# afe.net
KiCad netlist of a schematic drawn in Altium Designer
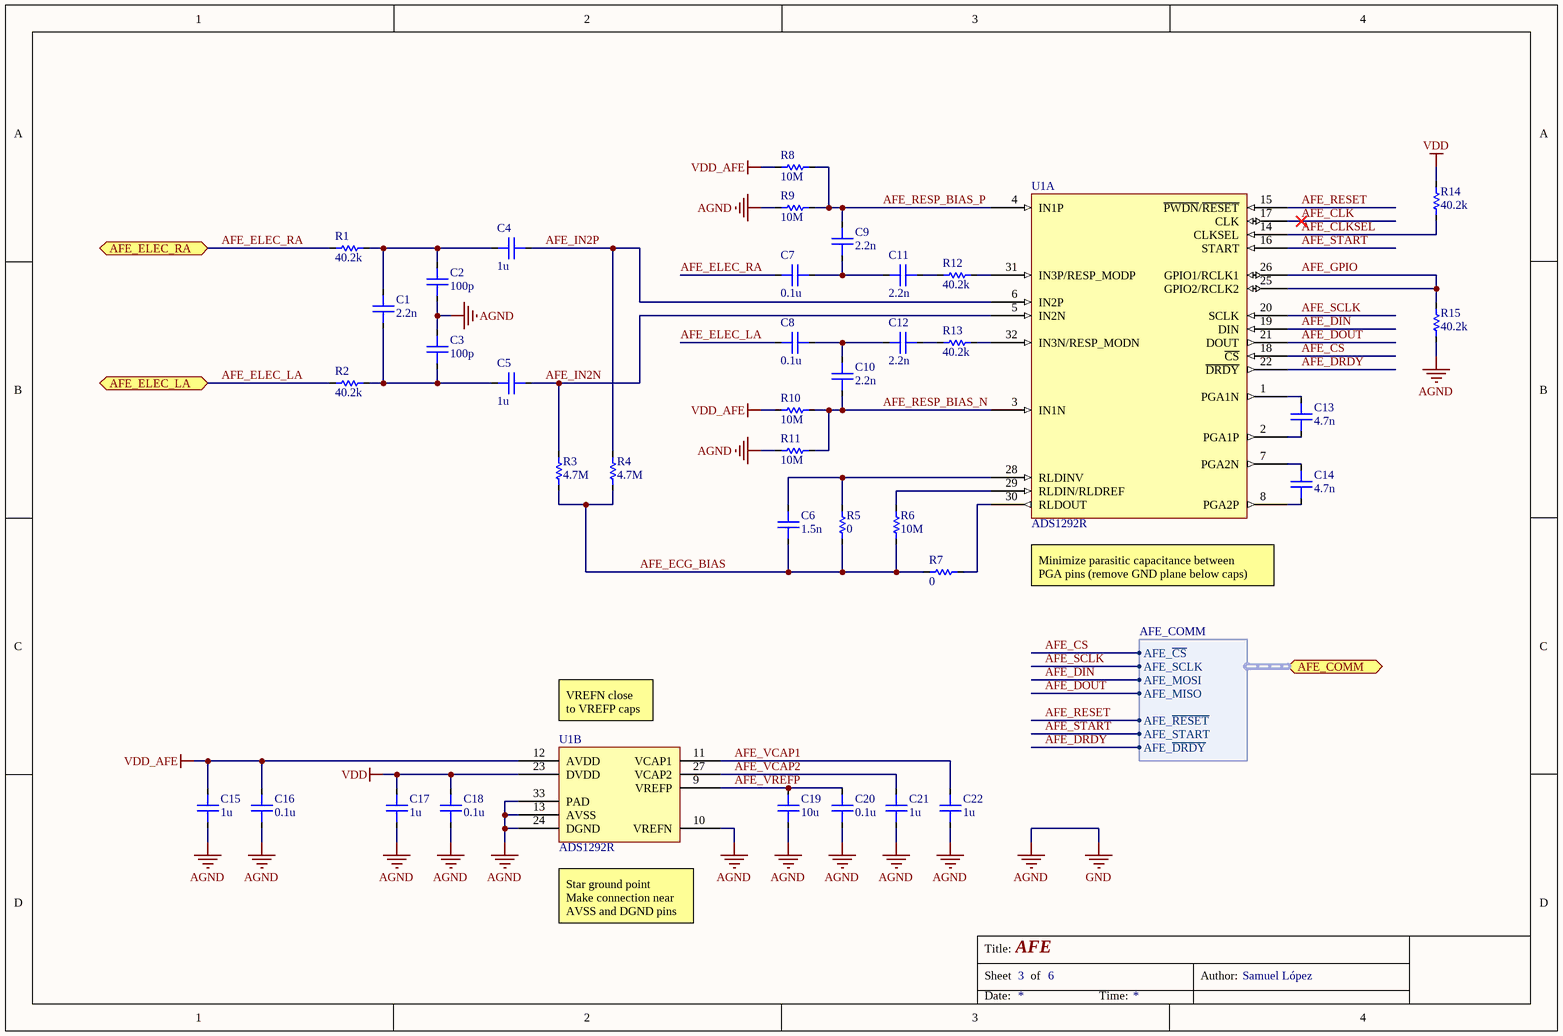
[diagram p0: afe.SchDoc]

(export (version "E")
  (design (tool "Eeschema 10.0.6"))
  (components
    (comp (ref "C1")
      (value "2.2n")
      (footprint "C0402")
      (description "Capacitor")
      (libsource (lib "misc") (part "Capacitor"))
    )
    (comp (ref "C2")
      (value "100p")
      (footprint "C0402")
      (description "Capacitor")
      (libsource (lib "misc") (part "Capacitor"))
    )
    (comp (ref "C3")
      (value "100p")
      (footprint "C0402")
      (description "Capacitor")
      (libsource (lib "misc") (part "Capacitor"))
    )
    (comp (ref "C4")
      (value "1u")
      (footprint "C0402")
      (description "Capacitor")
      (libsource (lib "misc") (part "Capacitor"))
    )
    (comp (ref "C5")
      (value "1u")
      (footprint "C0402")
      (description "Capacitor")
      (libsource (lib "misc") (part "Capacitor"))
    )
    (comp (ref "C6")
      (value "1.5n")
      (footprint "C0402")
      (description "Capacitor")
      (libsource (lib "misc") (part "Capacitor"))
    )
    (comp (ref "C7")
      (value "0.1u")
      (footprint "C0402")
      (description "Capacitor")
      (libsource (lib "misc") (part "Capacitor"))
    )
    (comp (ref "C8")
      (value "0.1u")
      (footprint "C0402")
      (description "Capacitor")
      (libsource (lib "misc") (part "Capacitor"))
    )
    (comp (ref "C9")
      (value "2.2n")
      (footprint "C0402")
      (description "Capacitor")
      (libsource (lib "misc") (part "Capacitor"))
    )
    (comp (ref "C10")
      (value "2.2n")
      (footprint "C0402")
      (description "Capacitor")
      (libsource (lib "misc") (part "Capacitor"))
    )
    (comp (ref "C11")
      (value "2.2n")
      (footprint "C0402")
      (description "Capacitor")
      (libsource (lib "misc") (part "Capacitor"))
    )
    (comp (ref "C12")
      (value "2.2n")
      (footprint "C0402")
      (description "Capacitor")
      (libsource (lib "misc") (part "Capacitor"))
    )
    (comp (ref "C13")
      (value "4.7n")
      (footprint "C0402")
      (description "Capacitor")
      (libsource (lib "misc") (part "Capacitor"))
    )
    (comp (ref "C14")
      (value "4.7n")
      (footprint "C0402")
      (description "Capacitor")
      (libsource (lib "misc") (part "Capacitor"))
    )
    (comp (ref "C15")
      (value "1u")
      (footprint "C0402")
      (description "Capacitor")
      (libsource (lib "misc") (part "Capacitor"))
    )
    (comp (ref "C16")
      (value "0.1u")
      (footprint "C0402")
      (description "Capacitor")
      (libsource (lib "misc") (part "Capacitor"))
    )
    (comp (ref "C17")
      (value "1u")
      (footprint "C0402")
      (description "Capacitor")
      (libsource (lib "misc") (part "Capacitor"))
    )
    (comp (ref "C18")
      (value "0.1u")
      (footprint "C0402")
      (description "Capacitor")
      (libsource (lib "misc") (part "Capacitor"))
    )
    (comp (ref "C19")
      (value "10u")
      (footprint "C0603")
      (description "Capacitor")
      (libsource (lib "misc") (part "Capacitor"))
    )
    (comp (ref "C20")
      (value "0.1u")
      (footprint "C0402")
      (description "Capacitor")
      (libsource (lib "misc") (part "Capacitor"))
    )
    (comp (ref "C21")
      (value "1u")
      (footprint "C0402")
      (description "Capacitor")
      (libsource (lib "misc") (part "Capacitor"))
    )
    (comp (ref "C22")
      (value "1u")
      (footprint "C0402")
      (description "Capacitor")
      (libsource (lib "misc") (part "Capacitor"))
    )
    (comp (ref "R1")
      (value "40.2k")
      (footprint "R0402")
      (description "Resistor")
      (libsource (lib "misc") (part "Resistor"))
    )
    (comp (ref "R2")
      (value "40.2k")
      (footprint "R0402")
      (description "Resistor")
      (libsource (lib "misc") (part "Resistor"))
    )
    (comp (ref "R3")
      (value "4.7M")
      (footprint "R0402")
      (description "Resistor")
      (libsource (lib "misc") (part "Resistor"))
    )
    (comp (ref "R4")
      (value "4.7M")
      (footprint "R0402")
      (description "Resistor")
      (libsource (lib "misc") (part "Resistor"))
    )
    (comp (ref "R5")
      (value "0")
      (footprint "R0402")
      (description "Resistor")
      (libsource (lib "misc") (part "Resistor"))
    )
    (comp (ref "R6")
      (value "10M")
      (footprint "R0402")
      (description "Resistor")
      (libsource (lib "misc") (part "Resistor"))
    )
    (comp (ref "R7")
      (value "0")
      (footprint "R0402")
      (description "Resistor")
      (libsource (lib "misc") (part "Resistor"))
    )
    (comp (ref "R8")
      (value "10M")
      (footprint "R0402")
      (description "Resistor")
      (libsource (lib "misc") (part "Resistor"))
    )
    (comp (ref "R9")
      (value "10M")
      (footprint "R0402")
      (description "Resistor")
      (libsource (lib "misc") (part "Resistor"))
    )
    (comp (ref "R10")
      (value "10M")
      (footprint "R0402")
      (description "Resistor")
      (libsource (lib "misc") (part "Resistor"))
    )
    (comp (ref "R11")
      (value "10M")
      (footprint "R0402")
      (description "Resistor")
      (libsource (lib "misc") (part "Resistor"))
    )
    (comp (ref "R12")
      (value "40.2k")
      (footprint "R0402")
      (description "Resistor")
      (libsource (lib "misc") (part "Resistor"))
    )
    (comp (ref "R13")
      (value "40.2k")
      (footprint "R0402")
      (description "Resistor")
      (libsource (lib "misc") (part "Resistor"))
    )
    (comp (ref "R14")
      (value "40.2k")
      (footprint "R0402")
      (description "Resistor")
      (libsource (lib "misc") (part "Resistor"))
    )
    (comp (ref "R15")
      (value "40.2k")
      (footprint "R0402")
      (description "Resistor")
      (libsource (lib "misc") (part "Resistor"))
    )
    (comp (ref "U1")
      (value "ADS1292R")
      (footprint "ADS129x_QFN")
      (description "IC - Analog Front End - Medical")
      (libsource (lib "ecg-go") (part "ADS1292R"))
    )
  )
  (nets
    (net (code "3") (name "/AFE_CLK") (class "Default")
      (node (ref "U1") (pin "17") (pinfunction "CLK_17") (pintype "bidirectional"))
    )
    (net (code "4") (name "/AFE_CLKSEL") (class "Default")
      (node (ref "R14") (pin "1") (pinfunction "1_1") (pintype "passive"))
      (node (ref "U1") (pin "14") (pinfunction "CLKSEL_14") (pintype "input"))
    )
    (net (code "5") (name "/AFE_CS") (class "Default")
      (node (ref "U1") (pin "18") (pinfunction "~{CS}_18") (pintype "input"))
    )
    (net (code "6") (name "/AFE_DIN") (class "Default")
      (node (ref "U1") (pin "19") (pinfunction "DIN_19") (pintype "input"))
    )
    (net (code "7") (name "/AFE_DOUT") (class "Default")
      (node (ref "U1") (pin "21") (pinfunction "DOUT_21") (pintype "output"))
    )
    (net (code "8") (name "/AFE_DRDY") (class "Default")
      (node (ref "U1") (pin "22") (pinfunction "~{DRDY}_22") (pintype "output"))
    )
    (net (code "9") (name "/AFE_ECG_BIAS") (class "Default")
      (node (ref "C6") (pin "1") (pinfunction "1_1") (pintype "passive"))
      (node (ref "R3") (pin "1") (pinfunction "1_1") (pintype "passive"))
      (node (ref "R4") (pin "1") (pinfunction "1_1") (pintype "passive"))
      (node (ref "R5") (pin "1") (pinfunction "1_1") (pintype "passive"))
      (node (ref "R6") (pin "1") (pinfunction "1_1") (pintype "passive"))
      (node (ref "R7") (pin "2") (pinfunction "2_2") (pintype "passive"))
    )
    (net (code "10") (name "/AFE_ELEC_LA") (class "Default")
      (node (ref "C8") (pin "1") (pinfunction "1_1") (pintype "passive"))
      (node (ref "R2") (pin "2") (pinfunction "2_2") (pintype "passive"))
    )
    (net (code "11") (name "/AFE_ELEC_RA") (class "Default")
      (node (ref "C7") (pin "2") (pinfunction "2_2") (pintype "passive"))
      (node (ref "R1") (pin "2") (pinfunction "2_2") (pintype "passive"))
    )
    (net (code "12") (name "/AFE_GPIO") (class "Default")
      (node (ref "R15") (pin "2") (pinfunction "2_2") (pintype "passive"))
      (node (ref "U1") (pin "25") (pinfunction "GPIO2/RCLK2_25") (pintype "bidirectional"))
      (node (ref "U1") (pin "26") (pinfunction "GPIO1/RCLK1_26") (pintype "bidirectional"))
    )
    (net (code "13") (name "/AFE_IN2N") (class "Default")
      (node (ref "C5") (pin "2") (pinfunction "2_2") (pintype "passive"))
      (node (ref "R3") (pin "2") (pinfunction "2_2") (pintype "passive"))
      (node (ref "U1") (pin "5") (pinfunction "IN2N_5") (pintype "input"))
    )
    (net (code "14") (name "/AFE_IN2P") (class "Default")
      (node (ref "C4") (pin "2") (pinfunction "2_2") (pintype "passive"))
      (node (ref "R4") (pin "2") (pinfunction "2_2") (pintype "passive"))
      (node (ref "U1") (pin "6") (pinfunction "IN2P_6") (pintype "input"))
    )
    (net (code "15") (name "/AFE_RESET") (class "Default")
      (node (ref "U1") (pin "15") (pinfunction "~{PWDN}/~{RESET}_15") (pintype "input"))
    )
    (net (code "16") (name "/AFE_RESP_BIAS_N") (class "Default")
      (node (ref "C10") (pin "1") (pinfunction "1_1") (pintype "passive"))
      (node (ref "R10") (pin "1") (pinfunction "1_1") (pintype "passive"))
      (node (ref "R11") (pin "1") (pinfunction "1_1") (pintype "passive"))
      (node (ref "U1") (pin "3") (pinfunction "IN1N_3") (pintype "input"))
    )
    (net (code "17") (name "/AFE_RESP_BIAS_P") (class "Default")
      (node (ref "C9") (pin "1") (pinfunction "1_1") (pintype "passive"))
      (node (ref "R8") (pin "1") (pinfunction "1_1") (pintype "passive"))
      (node (ref "R9") (pin "1") (pinfunction "1_1") (pintype "passive"))
      (node (ref "U1") (pin "4") (pinfunction "IN1P_4") (pintype "input"))
    )
    (net (code "18") (name "/AFE_SCLK") (class "Default")
      (node (ref "U1") (pin "20") (pinfunction "SCLK_20") (pintype "input"))
    )
    (net (code "19") (name "/AFE_START") (class "Default")
      (node (ref "U1") (pin "16") (pinfunction "START_16") (pintype "input"))
    )
    (net (code "20") (name "/AFE_VCAP1") (class "Default")
      (node (ref "C22") (pin "2") (pinfunction "2_2") (pintype "passive"))
      (node (ref "U1") (pin "11") (pinfunction "VCAP1_11") (pintype "passive"))
    )
    (net (code "21") (name "/AFE_VCAP2") (class "Default")
      (node (ref "C21") (pin "2") (pinfunction "2_2") (pintype "passive"))
      (node (ref "U1") (pin "27") (pinfunction "VCAP2_27") (pintype "passive"))
    )
    (net (code "23") (name "/AFE_VREFP") (class "Default")
      (node (ref "C19") (pin "2") (pinfunction "2_2") (pintype "passive"))
      (node (ref "C20") (pin "2") (pinfunction "2_2") (pintype "passive"))
      (node (ref "U1") (pin "9") (pinfunction "VREFP_9") (pintype "passive"))
    )
    (net (code "24") (name "AGND") (class "Default")
      (node (ref "C15") (pin "1") (pinfunction "1_1") (pintype "passive"))
      (node (ref "C16") (pin "1") (pinfunction "1_1") (pintype "passive"))
      (node (ref "C17") (pin "1") (pinfunction "1_1") (pintype "passive"))
      (node (ref "C18") (pin "1") (pinfunction "1_1") (pintype "passive"))
      (node (ref "C19") (pin "1") (pinfunction "1_1") (pintype "passive"))
      (node (ref "C2") (pin "2") (pinfunction "2_2") (pintype "passive"))
      (node (ref "C20") (pin "1") (pinfunction "1_1") (pintype "passive"))
      (node (ref "C21") (pin "1") (pinfunction "1_1") (pintype "passive"))
      (node (ref "C22") (pin "1") (pinfunction "1_1") (pintype "passive"))
      (node (ref "C3") (pin "1") (pinfunction "1_1") (pintype "passive"))
      (node (ref "R11") (pin "2") (pinfunction "2_2") (pintype "passive"))
      (node (ref "R15") (pin "1") (pinfunction "1_1") (pintype "passive"))
      (node (ref "R9") (pin "2") (pinfunction "2_2") (pintype "passive"))
      (node (ref "U1") (pin "10") (pinfunction "VREFN_10") (pintype "passive"))
      (node (ref "U1") (pin "13") (pinfunction "AVSS_13") (pintype "power_in"))
      (node (ref "U1") (pin "24") (pinfunction "DGND_24") (pintype "power_in"))
      (node (ref "U1") (pin "33") (pinfunction "PAD_33") (pintype "power_in"))
    )
    (net (code "25") (name "Net-(C1-Pad1)") (class "Default")
      (node (ref "C1") (pin "1") (pinfunction "1_1") (pintype "passive"))
      (node (ref "C2") (pin "1") (pinfunction "1_1") (pintype "passive"))
      (node (ref "C4") (pin "1") (pinfunction "1_1") (pintype "passive"))
      (node (ref "R1") (pin "1") (pinfunction "1_1") (pintype "passive"))
    )
    (net (code "26") (name "Net-(C1-Pad2)") (class "Default")
      (node (ref "C1") (pin "2") (pinfunction "2_2") (pintype "passive"))
      (node (ref "C3") (pin "2") (pinfunction "2_2") (pintype "passive"))
      (node (ref "C5") (pin "1") (pinfunction "1_1") (pintype "passive"))
      (node (ref "R2") (pin "1") (pinfunction "1_1") (pintype "passive"))
    )
    (net (code "27") (name "Net-(C10-Pad2)") (class "Default")
      (node (ref "C10") (pin "2") (pinfunction "2_2") (pintype "passive"))
      (node (ref "C12") (pin "1") (pinfunction "1_1") (pintype "passive"))
      (node (ref "C8") (pin "2") (pinfunction "2_2") (pintype "passive"))
    )
    (net (code "28") (name "Net-(C11-Pad1)") (class "Default")
      (node (ref "C11") (pin "1") (pinfunction "1_1") (pintype "passive"))
      (node (ref "R12") (pin "2") (pinfunction "2_2") (pintype "passive"))
    )
    (net (code "29") (name "Net-(C11-Pad2)") (class "Default")
      (node (ref "C11") (pin "2") (pinfunction "2_2") (pintype "passive"))
      (node (ref "C7") (pin "1") (pinfunction "1_1") (pintype "passive"))
      (node (ref "C9") (pin "2") (pinfunction "2_2") (pintype "passive"))
    )
    (net (code "30") (name "Net-(C12-Pad2)") (class "Default")
      (node (ref "C12") (pin "2") (pinfunction "2_2") (pintype "passive"))
      (node (ref "R13") (pin "2") (pinfunction "2_2") (pintype "passive"))
    )
    (net (code "31") (name "Net-(U1A-IN3N{slash}RESP_MODN)") (class "Default")
      (node (ref "R13") (pin "1") (pinfunction "1_1") (pintype "passive"))
      (node (ref "U1") (pin "32") (pinfunction "IN3N/RESP_MODN_32") (pintype "input"))
    )
    (net (code "32") (name "Net-(U1A-IN3P{slash}RESP_MODP)") (class "Default")
      (node (ref "R12") (pin "1") (pinfunction "1_1") (pintype "passive"))
      (node (ref "U1") (pin "31") (pinfunction "IN3P/RESP_MODP_31") (pintype "input"))
    )
    (net (code "33") (name "Net-(U1A-PGA1N)") (class "Default")
      (node (ref "C13") (pin "2") (pinfunction "2_2") (pintype "passive"))
      (node (ref "U1") (pin "1") (pinfunction "PGA1N_1") (pintype "output"))
    )
    (net (code "34") (name "Net-(U1A-PGA1P)") (class "Default")
      (node (ref "C13") (pin "1") (pinfunction "1_1") (pintype "passive"))
      (node (ref "U1") (pin "2") (pinfunction "PGA1P_2") (pintype "output"))
    )
    (net (code "35") (name "Net-(U1A-PGA2N)") (class "Default")
      (node (ref "C14") (pin "2") (pinfunction "2_2") (pintype "passive"))
      (node (ref "U1") (pin "7") (pinfunction "PGA2N_7") (pintype "output"))
    )
    (net (code "36") (name "Net-(U1A-PGA2P)") (class "Default")
      (node (ref "C14") (pin "1") (pinfunction "1_1") (pintype "passive"))
      (node (ref "U1") (pin "8") (pinfunction "PGA2P_8") (pintype "output"))
    )
    (net (code "37") (name "Net-(U1A-RLDINV)") (class "Default")
      (node (ref "C6") (pin "2") (pinfunction "2_2") (pintype "passive"))
      (node (ref "R5") (pin "2") (pinfunction "2_2") (pintype "passive"))
      (node (ref "U1") (pin "28") (pinfunction "RLDINV_28") (pintype "input"))
    )
    (net (code "38") (name "Net-(U1A-RLDIN{slash}RLDREF)") (class "Default")
      (node (ref "R6") (pin "2") (pinfunction "2_2") (pintype "passive"))
      (node (ref "U1") (pin "29") (pinfunction "RLDIN/RLDREF_29") (pintype "input"))
    )
    (net (code "39") (name "Net-(U1A-RLDOUT)") (class "Default")
      (node (ref "R7") (pin "1") (pinfunction "1_1") (pintype "passive"))
      (node (ref "U1") (pin "30") (pinfunction "RLDOUT_30") (pintype "output"))
    )
    (net (code "40") (name "VDD") (class "Default")
      (node (ref "C17") (pin "2") (pinfunction "2_2") (pintype "passive"))
      (node (ref "C18") (pin "2") (pinfunction "2_2") (pintype "passive"))
      (node (ref "R14") (pin "2") (pinfunction "2_2") (pintype "passive"))
      (node (ref "U1") (pin "23") (pinfunction "DVDD_23") (pintype "power_in"))
    )
    (net (code "41") (name "VDD_AFE") (class "Default")
      (node (ref "C15") (pin "2") (pinfunction "2_2") (pintype "passive"))
      (node (ref "C16") (pin "2") (pinfunction "2_2") (pintype "passive"))
      (node (ref "R10") (pin "2") (pinfunction "2_2") (pintype "passive"))
      (node (ref "R8") (pin "2") (pinfunction "2_2") (pintype "passive"))
      (node (ref "U1") (pin "12") (pinfunction "AVDD_12") (pintype "power_in"))
    )
  )
)
